# pll.net
KiCad netlist of a schematic drawn in EAGLE
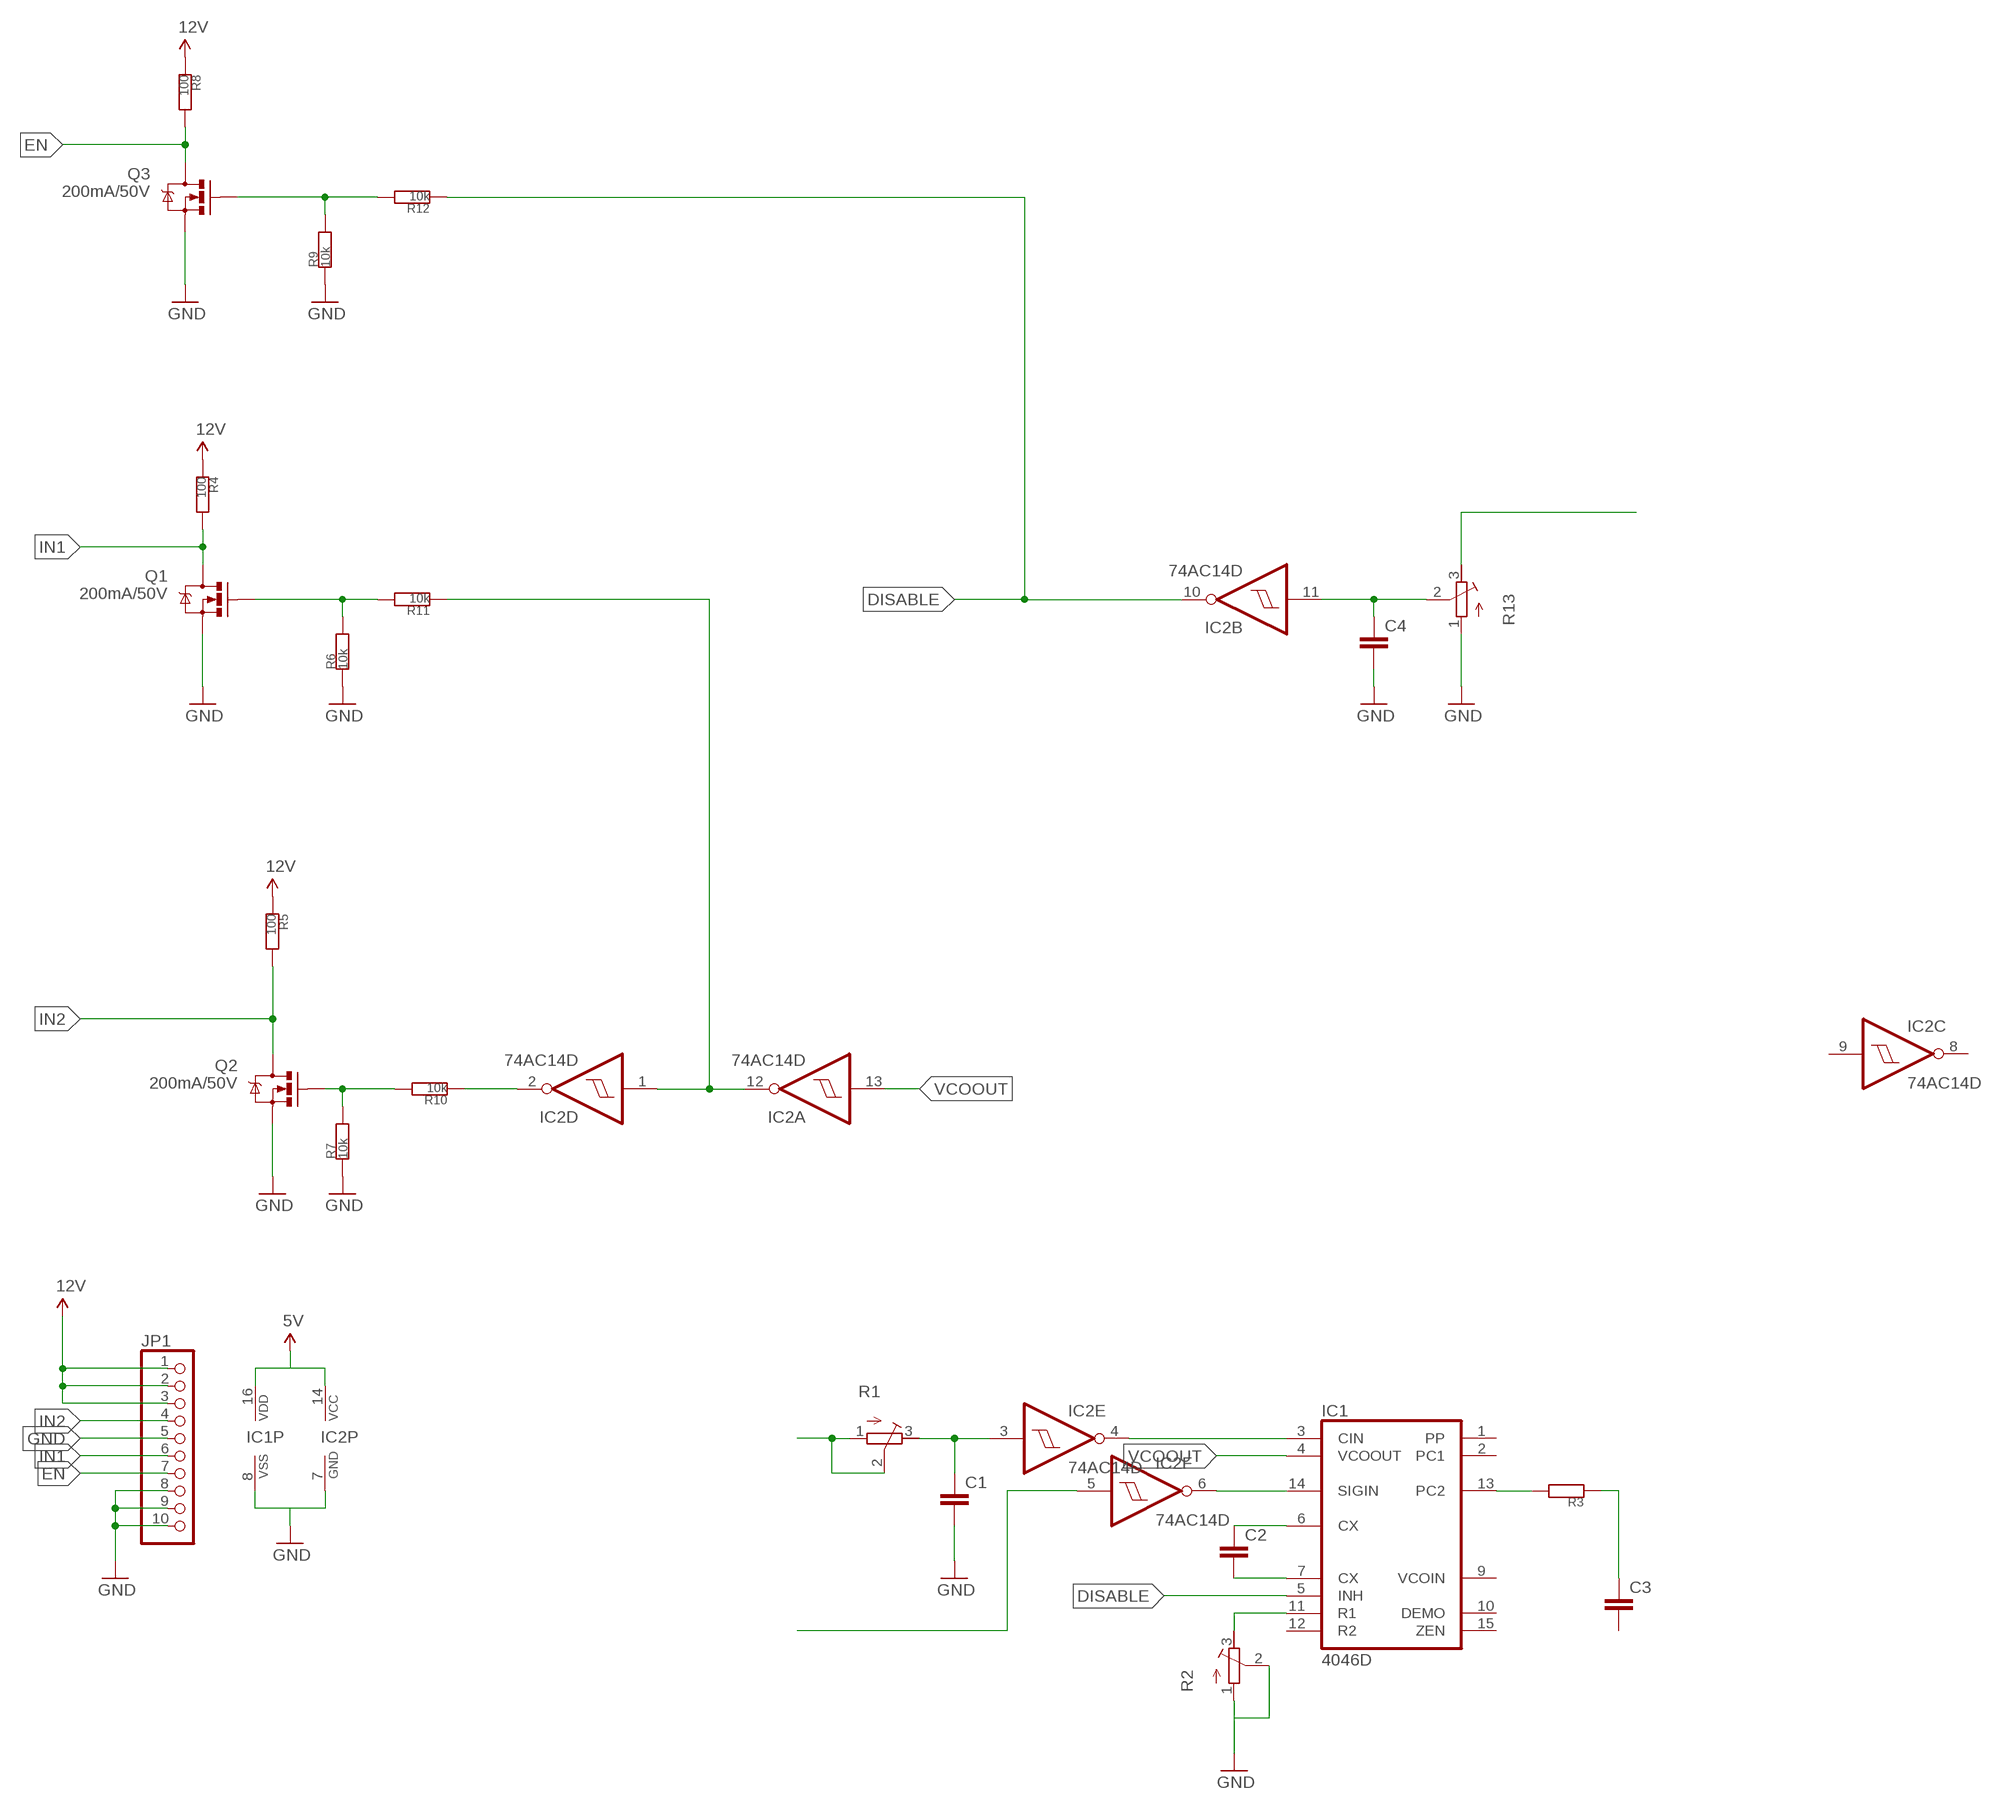
[diagram p0: schematic, sheet 1]

(export (version "E")
  (design (tool "Eeschema 10.0.6"))
  (components
    (comp (ref "C1")
      (value "CC0805")
      (footprint "eagle-import:C0805")
      (libsource (lib "eagle-import") (part "CC0805"))
    )
    (comp (ref "C2")
      (value "CC0805")
      (footprint "eagle-import:C0805")
      (libsource (lib "eagle-import") (part "CC0805"))
    )
    (comp (ref "C3")
      (value "CC0805")
      (footprint "eagle-import:C0805")
      (libsource (lib "eagle-import") (part "CC0805"))
    )
    (comp (ref "C4")
      (value "CC0805")
      (footprint "eagle-import:C0805")
      (libsource (lib "eagle-import") (part "CC0805"))
    )
    (comp (ref "IC1")
      (value "4046D")
      (footprint "eagle-import:SO16")
      (libsource (lib "eagle-import") (part "4046D"))
    )
    (comp (ref "IC2")
      (value "74AC14D")
      (footprint "eagle-import:SO14")
      (libsource (lib "eagle-import") (part "7414DAC"))
    )
    (comp (ref "JP1")
      (value "PINHD-1X10")
      (footprint "eagle-import:1X10")
      (libsource (lib "eagle-import") (part "PINHD-1X10"))
    )
    (comp (ref "Q1")
      (value "200mA/50V")
      (footprint "eagle-import:SOT23-3")
      (libsource (lib "eagle-import") (part "MOSFET-NCHANNELBSS138"))
    )
    (comp (ref "Q2")
      (value "200mA/50V")
      (footprint "eagle-import:SOT23-3")
      (libsource (lib "eagle-import") (part "MOSFET-NCHANNELBSS138"))
    )
    (comp (ref "Q3")
      (value "200mA/50V")
      (footprint "eagle-import:SOT23-3")
      (libsource (lib "eagle-import") (part "MOSFET-NCHANNELBSS138"))
    )
    (comp (ref "R1")
      (value "R-TRIMM64X")
      (footprint "eagle-import:RTRIM64X")
      (libsource (lib "eagle-import") (part "R-TRIMM64X"))
    )
    (comp (ref "R2")
      (value "R-TRIMM64X")
      (footprint "eagle-import:RTRIM64X")
      (libsource (lib "eagle-import") (part "R-TRIMM64X"))
    )
    (comp (ref "R3")
      (value "R0805")
      (footprint "eagle-import:R0805")
      (libsource (lib "eagle-import") (part "R0805"))
    )
    (comp (ref "R4")
      (value "100")
      (footprint "eagle-import:R0805")
      (libsource (lib "eagle-import") (part "R0805"))
    )
    (comp (ref "R5")
      (value "100")
      (footprint "eagle-import:R0805")
      (libsource (lib "eagle-import") (part "R0805"))
    )
    (comp (ref "R6")
      (value "10k")
      (footprint "eagle-import:0603")
      (libsource (lib "eagle-import") (part "R0603"))
    )
    (comp (ref "R7")
      (value "10k")
      (footprint "eagle-import:0603")
      (libsource (lib "eagle-import") (part "R0603"))
    )
    (comp (ref "R8")
      (value "100")
      (footprint "eagle-import:R0805")
      (libsource (lib "eagle-import") (part "R0805"))
    )
    (comp (ref "R9")
      (value "10k")
      (footprint "eagle-import:0603")
      (libsource (lib "eagle-import") (part "R0603"))
    )
    (comp (ref "R10")
      (value "10k")
      (footprint "eagle-import:R0805")
      (libsource (lib "eagle-import") (part "R0805"))
    )
    (comp (ref "R11")
      (value "10k")
      (footprint "eagle-import:0603")
      (libsource (lib "eagle-import") (part "R0603"))
    )
    (comp (ref "R12")
      (value "10k")
      (footprint "eagle-import:0603")
      (libsource (lib "eagle-import") (part "R0603"))
    )
    (comp (ref "R13")
      (value "R-TRIMM64X")
      (footprint "eagle-import:RTRIM64X")
      (libsource (lib "eagle-import") (part "R-TRIMM64X"))
    )
  )
  (nets
    (net (code "1") (name "5V") (class "Default")
      (node (ref "IC1") (pin "16") (pinfunction "VDD_16") (pintype "power_in"))
      (node (ref "IC2") (pin "14") (pinfunction "VCC_14") (pintype "power_in"))
    )
    (net (code "2") (name "12V") (class "Default")
      (node (ref "JP1") (pin "1") (pinfunction "1_1") (pintype "passive"))
      (node (ref "JP1") (pin "2") (pinfunction "2_2") (pintype "passive"))
      (node (ref "JP1") (pin "3") (pinfunction "3_3") (pintype "passive"))
      (node (ref "R4") (pin "1") (pinfunction "1_1") (pintype "passive"))
      (node (ref "R5") (pin "1") (pinfunction "1_1") (pintype "passive"))
      (node (ref "R8") (pin "1") (pinfunction "1_1") (pintype "passive"))
    )
    (net (code "3") (name "DISABLE") (class "Default")
      (node (ref "IC1") (pin "5") (pinfunction "INH_5") (pintype "input"))
      (node (ref "IC2") (pin "10") (pinfunction "O_10") (pintype "output"))
      (node (ref "R12") (pin "1") (pinfunction "1_1") (pintype "passive"))
    )
    (net (code "4") (name "EN") (class "Default")
      (node (ref "JP1") (pin "7") (pinfunction "7_7") (pintype "passive"))
      (node (ref "Q3") (pin "3") (pinfunction "D_3") (pintype "passive"))
      (node (ref "R8") (pin "2") (pinfunction "2_2") (pintype "passive"))
    )
    (net (code "5") (name "GND") (class "Default")
      (node (ref "C1") (pin "2") (pinfunction "2_2") (pintype "passive"))
      (node (ref "C4") (pin "2") (pinfunction "2_2") (pintype "passive"))
      (node (ref "IC1") (pin "8") (pinfunction "VSS_8") (pintype "power_in"))
      (node (ref "IC2") (pin "7") (pinfunction "GND_7") (pintype "power_in"))
      (node (ref "JP1") (pin "10") (pinfunction "10_10") (pintype "passive"))
      (node (ref "JP1") (pin "5") (pinfunction "5_5") (pintype "passive"))
      (node (ref "JP1") (pin "8") (pinfunction "8_8") (pintype "passive"))
      (node (ref "JP1") (pin "9") (pinfunction "9_9") (pintype "passive"))
      (node (ref "Q1") (pin "2") (pinfunction "S_2") (pintype "passive"))
      (node (ref "Q2") (pin "2") (pinfunction "S_2") (pintype "passive"))
      (node (ref "Q3") (pin "2") (pinfunction "S_2") (pintype "passive"))
      (node (ref "R13") (pin "1") (pinfunction "A_1") (pintype "passive"))
      (node (ref "R2") (pin "1") (pinfunction "A_1") (pintype "passive"))
      (node (ref "R2") (pin "2") (pinfunction "S_2") (pintype "passive"))
      (node (ref "R6") (pin "1") (pinfunction "1_1") (pintype "passive"))
      (node (ref "R7") (pin "1") (pinfunction "1_1") (pintype "passive"))
      (node (ref "R9") (pin "1") (pinfunction "1_1") (pintype "passive"))
    )
    (net (code "6") (name "IN1") (class "Default")
      (node (ref "JP1") (pin "6") (pinfunction "6_6") (pintype "passive"))
      (node (ref "Q1") (pin "3") (pinfunction "D_3") (pintype "passive"))
      (node (ref "R4") (pin "2") (pinfunction "2_2") (pintype "passive"))
    )
    (net (code "7") (name "IN2") (class "Default")
      (node (ref "JP1") (pin "4") (pinfunction "4_4") (pintype "passive"))
      (node (ref "Q2") (pin "3") (pinfunction "D_3") (pintype "passive"))
      (node (ref "R5") (pin "2") (pinfunction "2_2") (pintype "passive"))
    )
    (net (code "8") (name "Net-(C2-Pad1)") (class "Default")
      (node (ref "C2") (pin "1") (pinfunction "1_1") (pintype "passive"))
      (node (ref "IC1") (pin "6") (pinfunction "CX_6") (pintype "input"))
    )
    (net (code "9") (name "Net-(C2-Pad2)") (class "Default")
      (node (ref "C2") (pin "2") (pinfunction "2_2") (pintype "passive"))
      (node (ref "IC1") (pin "7") (pinfunction "CX_7") (pintype "input"))
    )
    (net (code "10") (name "Net-(C3-Pad1)") (class "Default")
      (node (ref "C3") (pin "1") (pinfunction "1_1") (pintype "passive"))
      (node (ref "R3") (pin "1") (pinfunction "1_1") (pintype "passive"))
    )
    (net (code "11") (name "Net-(IC1A-CIN)") (class "Default")
      (node (ref "IC1") (pin "3") (pinfunction "CIN_3") (pintype "input"))
      (node (ref "IC2") (pin "4") (pinfunction "O_4") (pintype "output"))
    )
    (net (code "12") (name "Net-(IC1A-PC2)") (class "Default")
      (node (ref "IC1") (pin "13") (pinfunction "PC2_13") (pintype "output"))
      (node (ref "R3") (pin "2") (pinfunction "2_2") (pintype "passive"))
    )
    (net (code "13") (name "Net-(IC1A-R1)") (class "Default")
      (node (ref "IC1") (pin "11") (pinfunction "R1_11") (pintype "input"))
      (node (ref "R2") (pin "3") (pinfunction "E_3") (pintype "passive"))
    )
    (net (code "14") (name "Net-(IC1A-SIGIN)") (class "Default")
      (node (ref "IC1") (pin "14") (pinfunction "SIGIN_14") (pintype "input"))
      (node (ref "IC2") (pin "6") (pinfunction "O_6") (pintype "output"))
    )
    (net (code "15") (name "Net-(IC2A-O)") (class "Default")
      (node (ref "IC2") (pin "1") (pinfunction "I_1") (pintype "input"))
      (node (ref "IC2") (pin "12") (pinfunction "O_12") (pintype "output"))
      (node (ref "R11") (pin "1") (pinfunction "1_1") (pintype "passive"))
    )
    (net (code "16") (name "Net-(IC2B-I)") (class "Default")
      (node (ref "C4") (pin "1") (pinfunction "1_1") (pintype "passive"))
      (node (ref "IC2") (pin "11") (pinfunction "I_11") (pintype "input"))
      (node (ref "R13") (pin "2") (pinfunction "S_2") (pintype "passive"))
    )
    (net (code "17") (name "Net-(IC2D-O)") (class "Default")
      (node (ref "IC2") (pin "2") (pinfunction "O_2") (pintype "output"))
      (node (ref "R10") (pin "1") (pinfunction "1_1") (pintype "passive"))
    )
    (net (code "18") (name "Net-(IC2E-I)") (class "Default")
      (node (ref "C1") (pin "1") (pinfunction "1_1") (pintype "passive"))
      (node (ref "IC2") (pin "3") (pinfunction "I_3") (pintype "input"))
      (node (ref "R1") (pin "3") (pinfunction "E_3") (pintype "passive"))
    )
    (net (code "19") (name "Net-(Q1-G)") (class "Default")
      (node (ref "Q1") (pin "1") (pinfunction "G_1") (pintype "passive"))
      (node (ref "R11") (pin "2") (pinfunction "2_2") (pintype "passive"))
      (node (ref "R6") (pin "2") (pinfunction "2_2") (pintype "passive"))
    )
    (net (code "20") (name "Net-(Q2-G)") (class "Default")
      (node (ref "Q2") (pin "1") (pinfunction "G_1") (pintype "passive"))
      (node (ref "R10") (pin "2") (pinfunction "2_2") (pintype "passive"))
      (node (ref "R7") (pin "2") (pinfunction "2_2") (pintype "passive"))
    )
    (net (code "21") (name "Net-(Q3-G)") (class "Default")
      (node (ref "Q3") (pin "1") (pinfunction "G_1") (pintype "passive"))
      (node (ref "R12") (pin "2") (pinfunction "2_2") (pintype "passive"))
      (node (ref "R9") (pin "2") (pinfunction "2_2") (pintype "passive"))
    )
    (net (code "22") (name "Net-(R1-A)") (class "Default")
      (node (ref "R1") (pin "1") (pinfunction "A_1") (pintype "passive"))
      (node (ref "R1") (pin "2") (pinfunction "S_2") (pintype "passive"))
    )
    (net (code "23") (name "VCOOUT") (class "Default")
      (node (ref "IC1") (pin "4") (pinfunction "VCOOUT_4") (pintype "output"))
      (node (ref "IC2") (pin "13") (pinfunction "I_13") (pintype "input"))
    )
    (net (code "24") (name "unconnected-(C3-Pad2)") (class "Default")
      (node (ref "C3") (pin "2") (pinfunction "2_2") (pintype "passive"))
    )
    (net (code "25") (name "unconnected-(IC1A-DEMO-Pad10)") (class "Default")
      (node (ref "IC1") (pin "10") (pinfunction "DEMO_10") (pintype "output"))
    )
    (net (code "26") (name "unconnected-(IC1A-PC1-Pad2)") (class "Default")
      (node (ref "IC1") (pin "2") (pinfunction "PC1_2") (pintype "output"))
    )
    (net (code "27") (name "unconnected-(IC1A-PP-Pad1)") (class "Default")
      (node (ref "IC1") (pin "1") (pinfunction "PP_1") (pintype "output"))
    )
    (net (code "28") (name "unconnected-(IC1A-R2-Pad12)") (class "Default")
      (node (ref "IC1") (pin "12") (pinfunction "R2_12") (pintype "input"))
    )
    (net (code "29") (name "unconnected-(IC1A-VCOIN-Pad9)") (class "Default")
      (node (ref "IC1") (pin "9") (pinfunction "VCOIN_9") (pintype "input"))
    )
    (net (code "30") (name "unconnected-(IC1A-ZEN-Pad15)") (class "Default")
      (node (ref "IC1") (pin "15") (pinfunction "ZEN_15") (pintype "input"))
    )
    (net (code "31") (name "unconnected-(IC2C-I-Pad9)") (class "Default")
      (node (ref "IC2") (pin "9") (pinfunction "I_9") (pintype "input"))
    )
    (net (code "32") (name "unconnected-(IC2C-O-Pad8)") (class "Default")
      (node (ref "IC2") (pin "8") (pinfunction "O_8") (pintype "output"))
    )
    (net (code "33") (name "unconnected-(IC2F-I-Pad5)") (class "Default")
      (node (ref "IC2") (pin "5") (pinfunction "I_5") (pintype "input"))
    )
    (net (code "34") (name "unconnected-(R13-E-Pad3)") (class "Default")
      (node (ref "R13") (pin "3") (pinfunction "E_3") (pintype "passive"))
    )
  )
)
